# HATv1.net
KiCad netlist of a schematic drawn in EAGLE
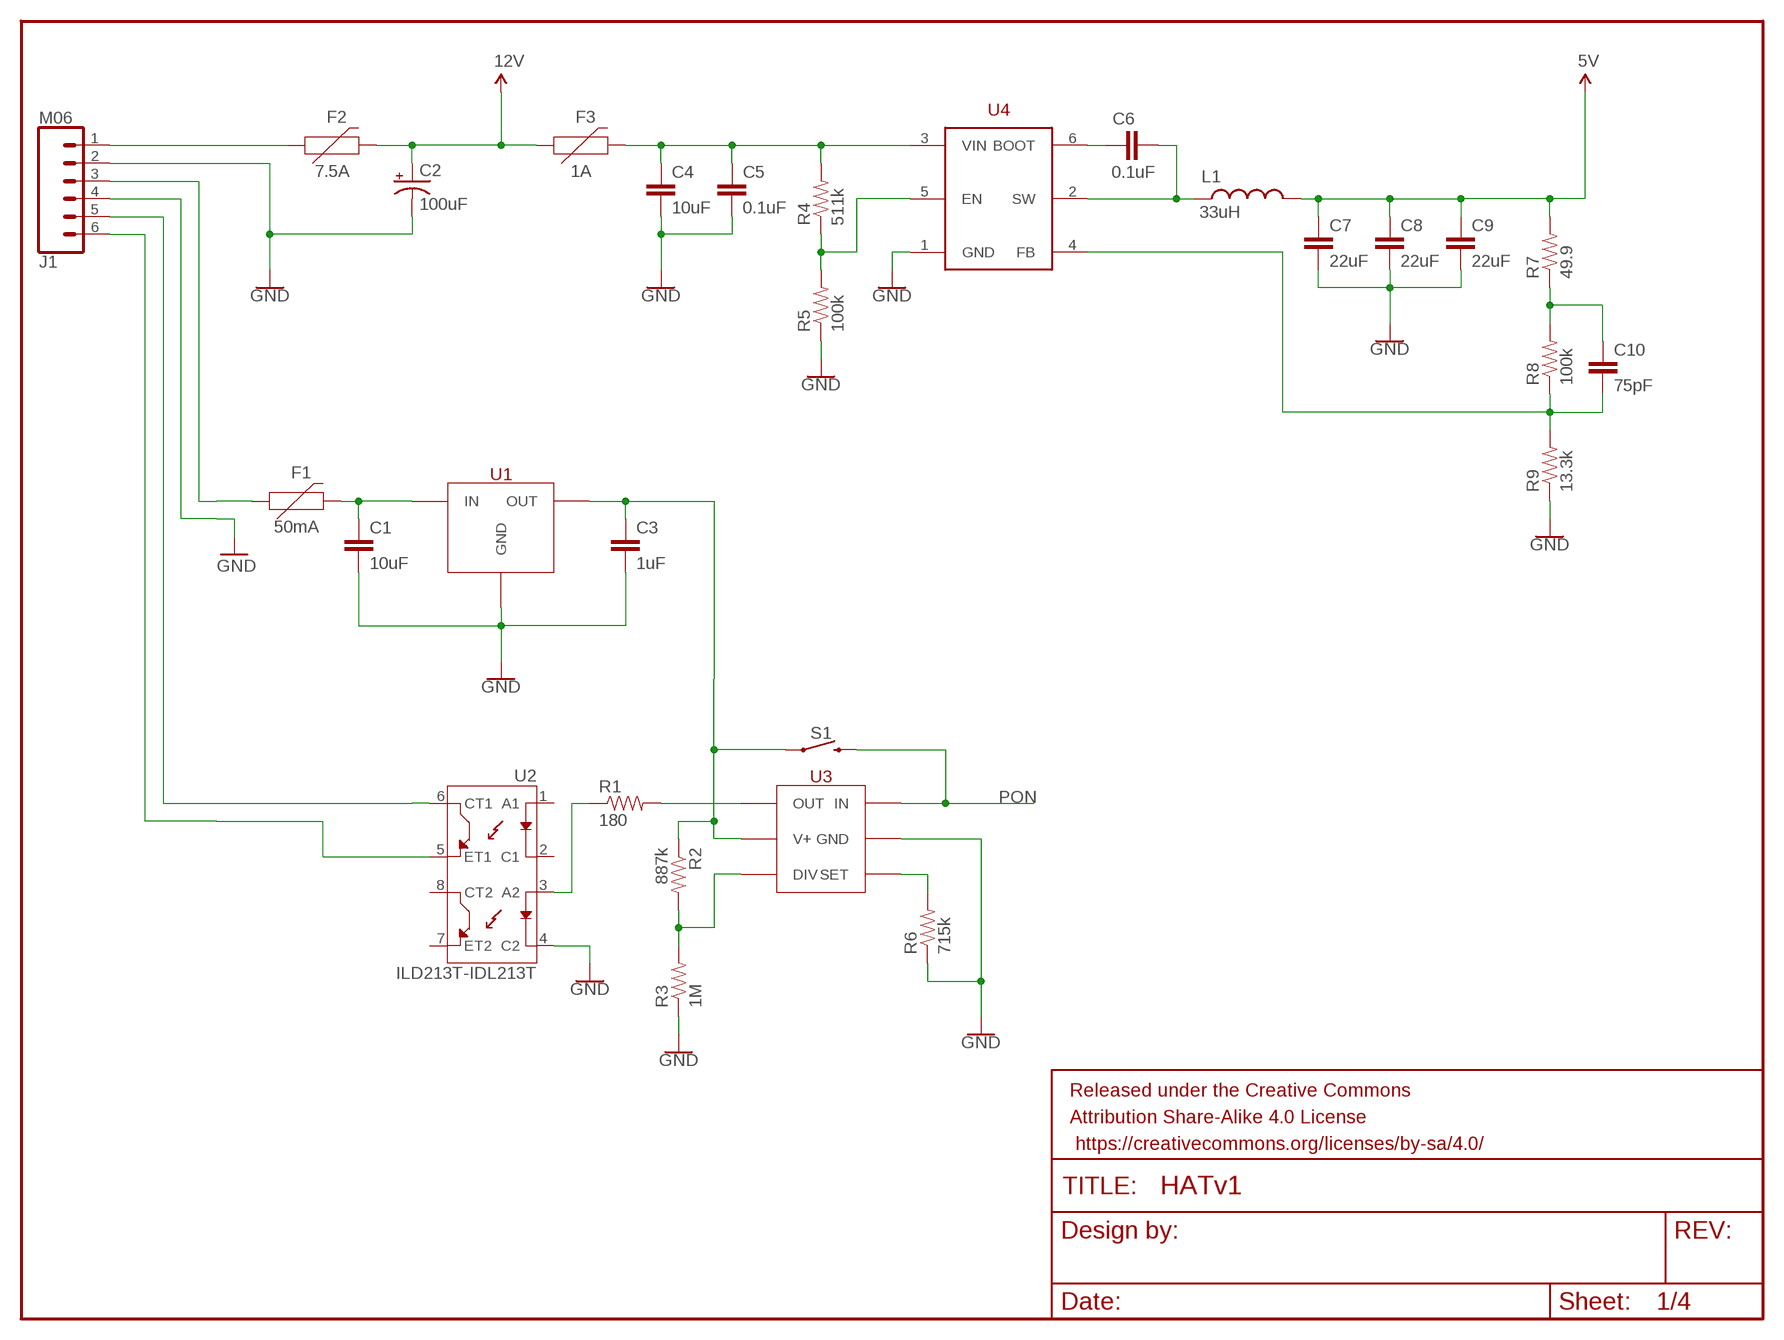
[diagram p0: schematic, sheet 1]
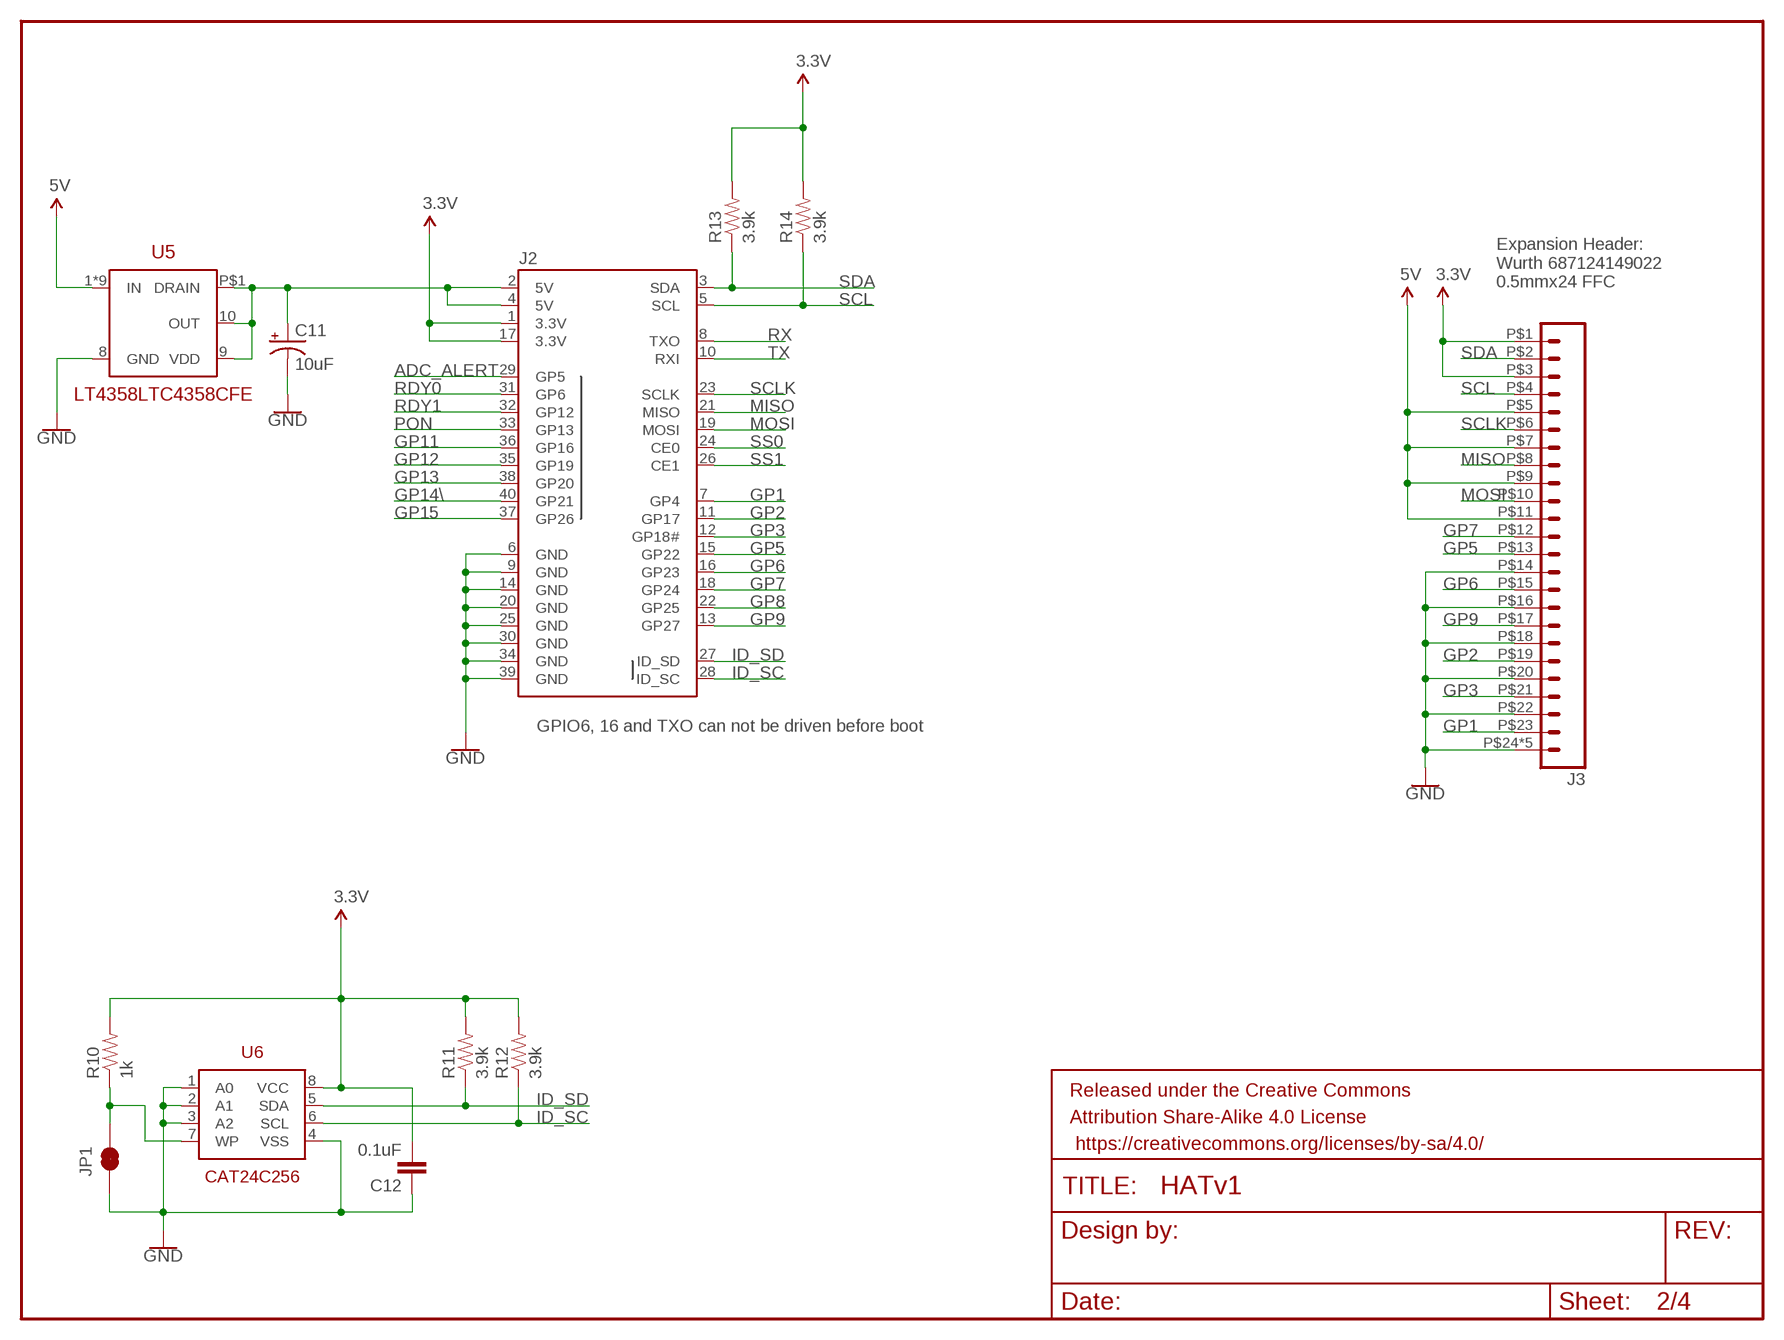
[diagram p1: schematic, sheet 2]
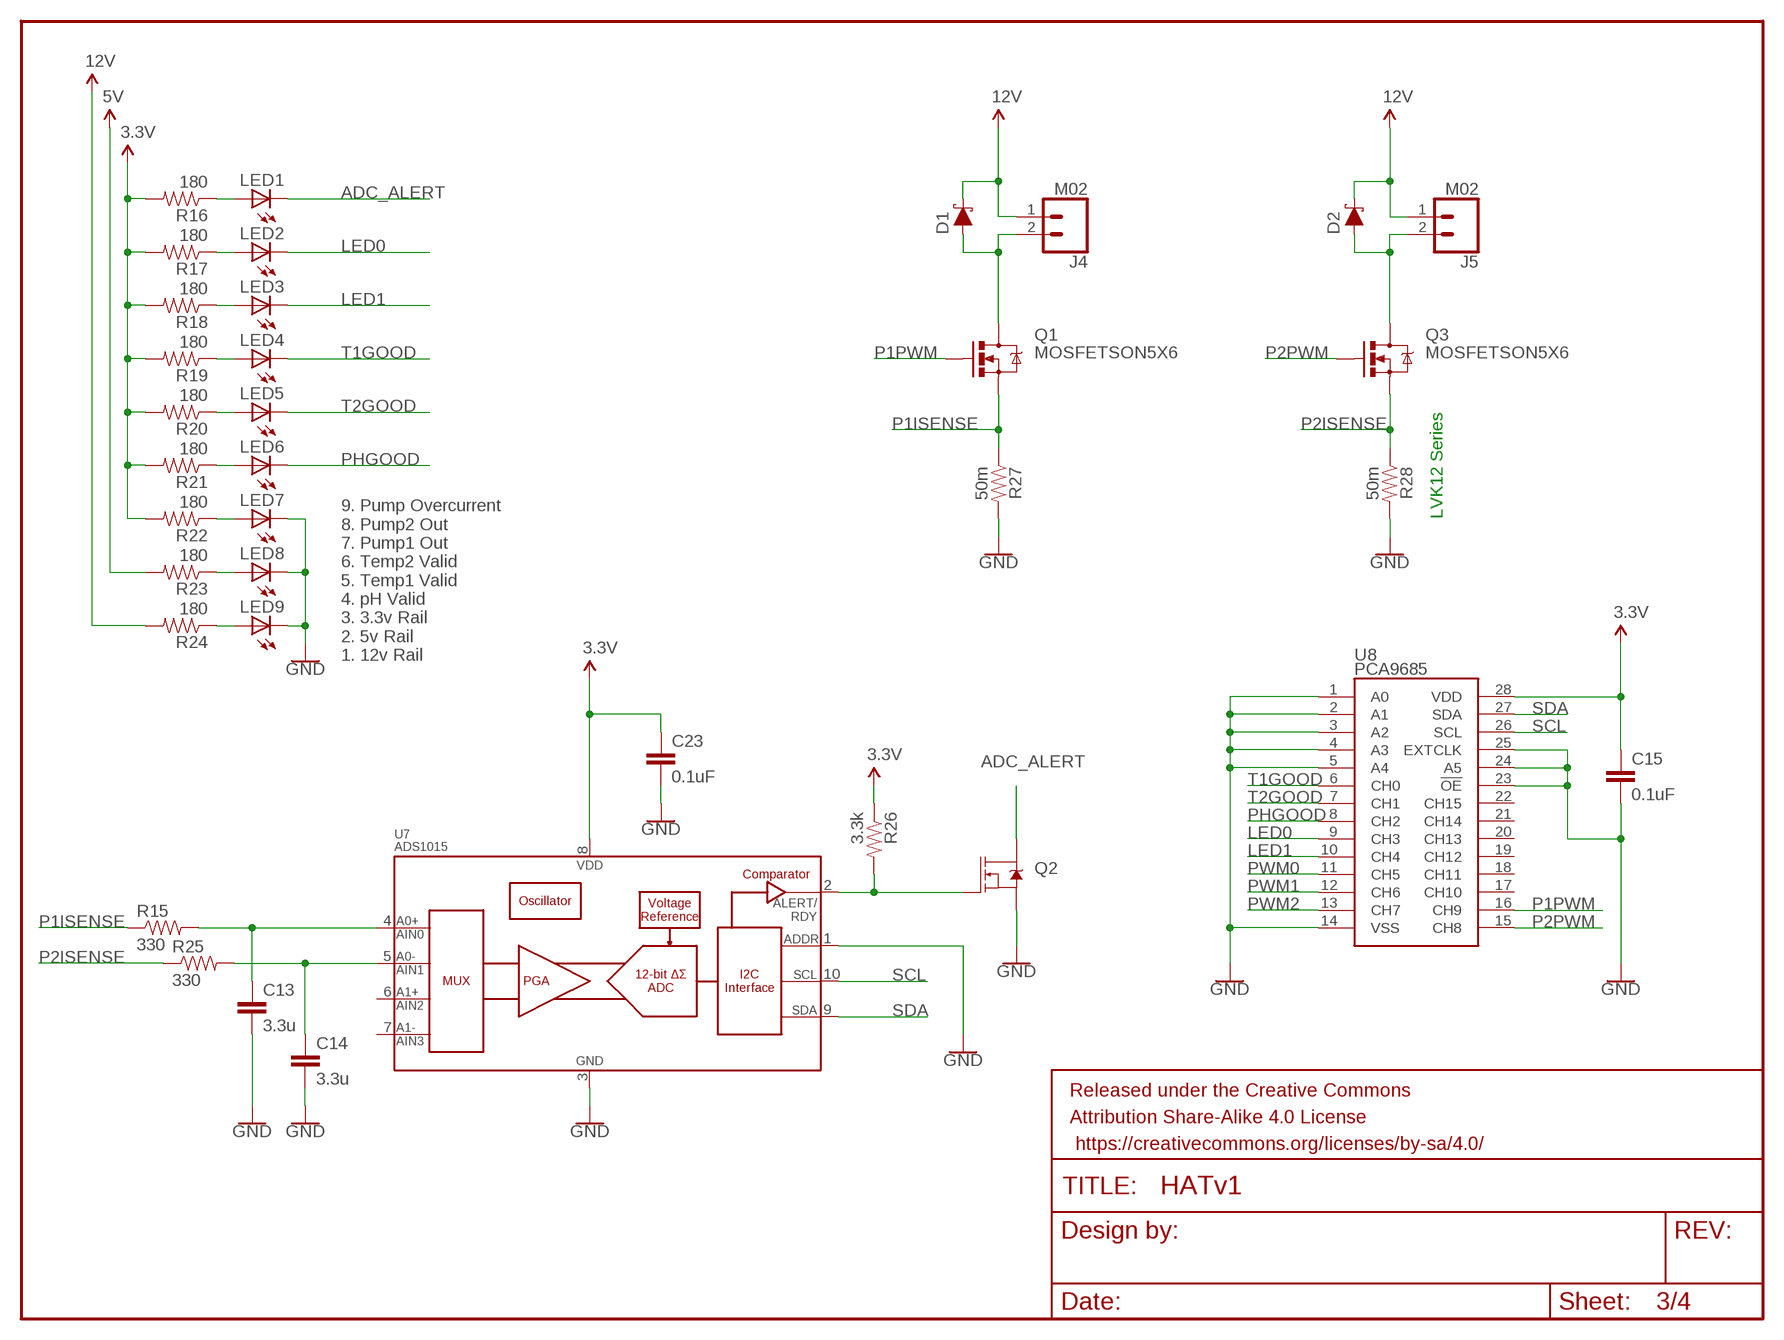
[diagram p2: schematic, sheet 3]
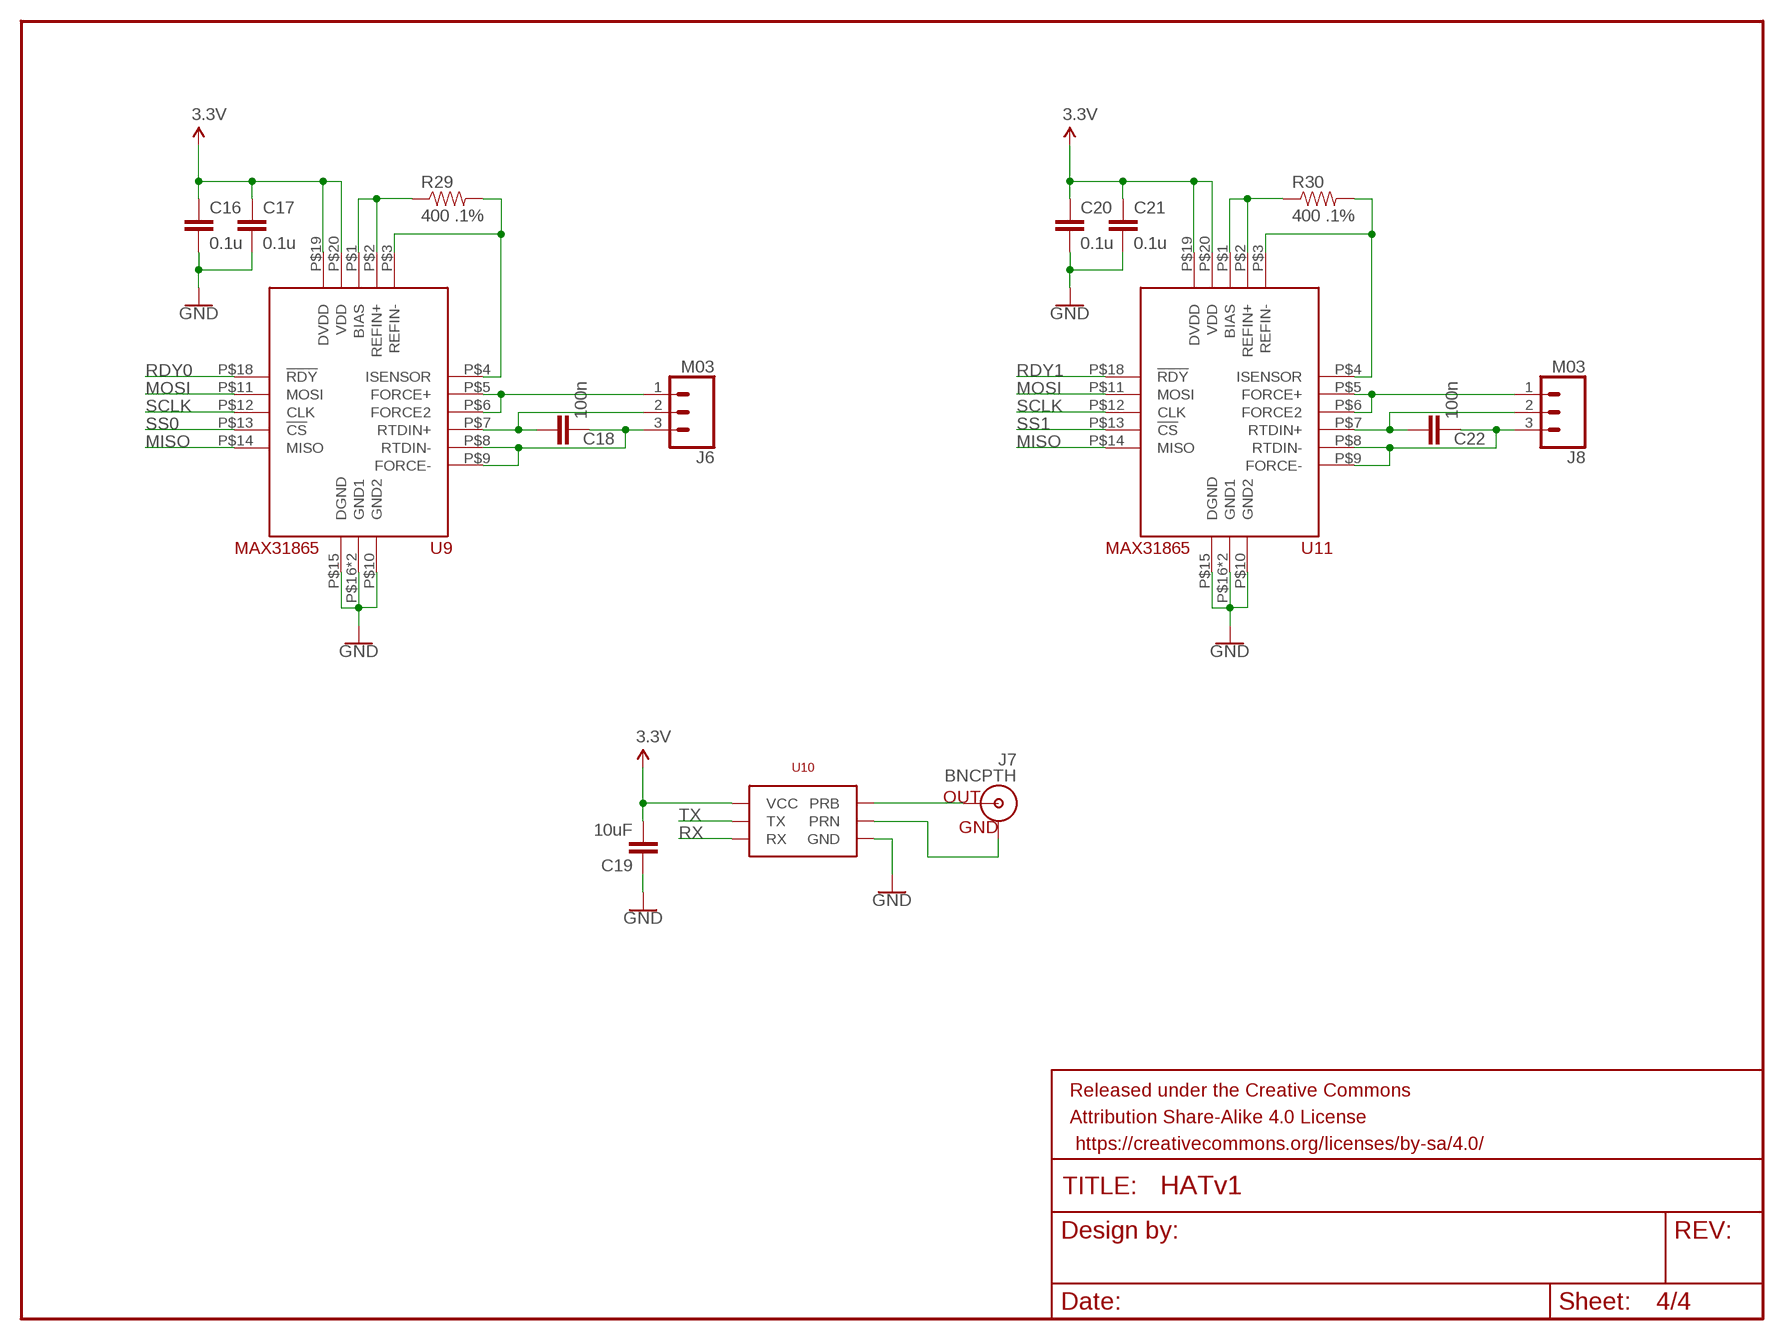
[diagram p3: schematic, sheet 4]

(export (version "E")
  (design (tool "Eeschema 10.0.6"))
  (components
    (comp (ref "C16")
      (value "0.1u")
      (footprint "eagle-import:0603-CAP")
      (libsource (lib "eagle-import") (part "CAP0603-CAP"))
    )
    (comp (ref "C17")
      (value "0.1u")
      (footprint "eagle-import:0603-CAP")
      (libsource (lib "eagle-import") (part "CAP0603-CAP"))
    )
    (comp (ref "C18")
      (value "100n")
      (footprint "eagle-import:0603-CAP")
      (libsource (lib "eagle-import") (part "CAP0603-CAP"))
    )
    (comp (ref "C19")
      (value "10uF")
      (footprint "eagle-import:1206")
      (libsource (lib "eagle-import") (part "10UF-1206-6.3V-20%"))
    )
    (comp (ref "C20")
      (value "0.1u")
      (footprint "eagle-import:0603-CAP")
      (libsource (lib "eagle-import") (part "CAP0603-CAP"))
    )
    (comp (ref "C21")
      (value "0.1u")
      (footprint "eagle-import:0603-CAP")
      (libsource (lib "eagle-import") (part "CAP0603-CAP"))
    )
    (comp (ref "C22")
      (value "100n")
      (footprint "eagle-import:0603-CAP")
      (libsource (lib "eagle-import") (part "CAP0603-CAP"))
    )
    (comp (ref "FRAME4")
      (value "FRAME-LETTERNO_PACKAGE")
      (footprint "eagle-import:DUMMY")
      (fields (field (name "DESIGNER") "Nobody"))
      (libsource (lib "eagle-import") (part "SparkFun-Aesthetics_507_FRAME-LETTERNO_PACKAGE"))
    )
    (comp (ref "J6")
      (value "M03")
      (footprint "eagle-import:1X03")
      (libsource (lib "eagle-import") (part "M03"))
    )
    (comp (ref "J7")
      (value "BNCPTH")
      (footprint "eagle-import:BNC")
      (libsource (lib "eagle-import") (part "BNCPTH"))
    )
    (comp (ref "J8")
      (value "M03")
      (footprint "eagle-import:1X03")
      (libsource (lib "eagle-import") (part "M03"))
    )
    (comp (ref "R29")
      (value "400 .1%")
      (footprint "eagle-import:0603-RES")
      (libsource (lib "eagle-import") (part "RESISTOR0603-RES"))
    )
    (comp (ref "R30")
      (value "400 .1%")
      (footprint "eagle-import:0603-RES")
      (libsource (lib "eagle-import") (part "RESISTOR0603-RES"))
    )
    (comp (ref "U9")
      (value "MAX31865")
      (footprint "eagle-import:TQFN20")
      (libsource (lib "eagle-import") (part "MAX31865"))
    )
    (comp (ref "U10")
      (value "EZOPH")
      (footprint "eagle-import:EZOPH")
      (libsource (lib "eagle-import") (part "EZOPH"))
    )
    (comp (ref "U11")
      (value "MAX31865")
      (footprint "eagle-import:TQFN20")
      (libsource (lib "eagle-import") (part "MAX31865"))
    )
    (comp (ref "C13")
      (value "3.3u")
      (footprint "eagle-import:0603")
      (libsource (lib "eagle-import") (part "2.2UF-0603-10V-20%"))
    )
    (comp (ref "C14")
      (value "3.3u")
      (footprint "eagle-import:0603")
      (libsource (lib "eagle-import") (part "2.2UF-0603-10V-20%"))
    )
    (comp (ref "C15")
      (value "0.1uF")
      (footprint "eagle-import:0603-CAP")
      (libsource (lib "eagle-import") (part "CAP0603-CAP"))
    )
    (comp (ref "C23")
      (value "0.1uF")
      (footprint "eagle-import:0603-CAP")
      (libsource (lib "eagle-import") (part "CAP0603-CAP"))
    )
    (comp (ref "D1")
      (value "DIODE-SCHOTTKY-B340A")
      (footprint "eagle-import:SMA-DIODE")
      (libsource (lib "eagle-import") (part "DIODE-SCHOTTKY-B340A"))
    )
    (comp (ref "D2")
      (value "DIODE-SCHOTTKY-B340A")
      (footprint "eagle-import:SMA-DIODE")
      (libsource (lib "eagle-import") (part "DIODE-SCHOTTKY-B340A"))
    )
    (comp (ref "FRAME3")
      (value "FRAME-LETTERNO_PACKAGE")
      (footprint "eagle-import:DUMMY")
      (fields (field (name "DESIGNER") "Nobody"))
      (libsource (lib "eagle-import") (part "FRAME-LETTERNO_PACKAGE"))
    )
    (comp (ref "J4")
      (value "M02")
      (footprint "eagle-import:SCREWTERMINAL-3.5MM-2")
      (libsource (lib "eagle-import") (part "M02"))
    )
    (comp (ref "J5")
      (value "M02")
      (footprint "eagle-import:SCREWTERMINAL-3.5MM-2")
      (libsource (lib "eagle-import") (part "M02"))
    )
    (comp (ref "LED1")
      (value "LEDCHIP-LED0603")
      (footprint "eagle-import:CHIP-LED0603")
      (libsource (lib "eagle-import") (part "LEDCHIP-LED0603"))
    )
    (comp (ref "LED2")
      (value "LEDCHIP-LED0603")
      (footprint "eagle-import:CHIP-LED0603")
      (libsource (lib "eagle-import") (part "LEDCHIP-LED0603"))
    )
    (comp (ref "LED3")
      (value "LEDCHIP-LED0603")
      (footprint "eagle-import:CHIP-LED0603")
      (libsource (lib "eagle-import") (part "LEDCHIP-LED0603"))
    )
    (comp (ref "LED4")
      (value "LEDCHIP-LED0603")
      (footprint "eagle-import:CHIP-LED0603")
      (libsource (lib "eagle-import") (part "LEDCHIP-LED0603"))
    )
    (comp (ref "LED5")
      (value "LEDCHIP-LED0603")
      (footprint "eagle-import:CHIP-LED0603")
      (libsource (lib "eagle-import") (part "LEDCHIP-LED0603"))
    )
    (comp (ref "LED6")
      (value "LEDCHIP-LED0603")
      (footprint "eagle-import:CHIP-LED0603")
      (libsource (lib "eagle-import") (part "LEDCHIP-LED0603"))
    )
    (comp (ref "LED7")
      (value "LEDCHIP-LED0603")
      (footprint "eagle-import:CHIP-LED0603")
      (libsource (lib "eagle-import") (part "LEDCHIP-LED0603"))
    )
    (comp (ref "LED8")
      (value "LEDCHIP-LED0603")
      (footprint "eagle-import:CHIP-LED0603")
      (libsource (lib "eagle-import") (part "LEDCHIP-LED0603"))
    )
    (comp (ref "LED9")
      (value "LEDCHIP-LED0603")
      (footprint "eagle-import:CHIP-LED0603")
      (libsource (lib "eagle-import") (part "LEDCHIP-LED0603"))
    )
    (comp (ref "Q1")
      (value "MOSFETSON5X6")
      (footprint "eagle-import:SON5X6MM")
      (libsource (lib "eagle-import") (part "MOSFETSON5X6"))
    )
    (comp (ref "Q2")
      (value "MOSFET-NCH-BSS138")
      (footprint "eagle-import:SOT23-3")
      (libsource (lib "eagle-import") (part "MOSFET-NCH-BSS138"))
    )
    (comp (ref "Q3")
      (value "MOSFETSON5X6")
      (footprint "eagle-import:SON5X6MM")
      (libsource (lib "eagle-import") (part "MOSFETSON5X6"))
    )
    (comp (ref "R15")
      (value "330")
      (footprint "eagle-import:0603-RES")
      (libsource (lib "eagle-import") (part "RESISTOR0603-RES"))
    )
    (comp (ref "R16")
      (value "180")
      (footprint "eagle-import:0603-RES")
      (libsource (lib "eagle-import") (part "RESISTOR0603-RES"))
    )
    (comp (ref "R17")
      (value "180")
      (footprint "eagle-import:0603-RES")
      (libsource (lib "eagle-import") (part "RESISTOR0603-RES"))
    )
    (comp (ref "R18")
      (value "180")
      (footprint "eagle-import:0603-RES")
      (libsource (lib "eagle-import") (part "RESISTOR0603-RES"))
    )
    (comp (ref "R19")
      (value "180")
      (footprint "eagle-import:0603-RES")
      (libsource (lib "eagle-import") (part "RESISTOR0603-RES"))
    )
    (comp (ref "R20")
      (value "180")
      (footprint "eagle-import:0603-RES")
      (libsource (lib "eagle-import") (part "RESISTOR0603-RES"))
    )
    (comp (ref "R21")
      (value "180")
      (footprint "eagle-import:0603-RES")
      (libsource (lib "eagle-import") (part "RESISTOR0603-RES"))
    )
    (comp (ref "R22")
      (value "180")
      (footprint "eagle-import:0603-RES")
      (libsource (lib "eagle-import") (part "RESISTOR0603-RES"))
    )
    (comp (ref "R23")
      (value "180")
      (footprint "eagle-import:0603-RES")
      (libsource (lib "eagle-import") (part "RESISTOR0603-RES"))
    )
    (comp (ref "R24")
      (value "180")
      (footprint "eagle-import:0603-RES")
      (libsource (lib "eagle-import") (part "RESISTOR0603-RES"))
    )
    (comp (ref "R25")
      (value "330")
      (footprint "eagle-import:0603-RES")
      (libsource (lib "eagle-import") (part "RESISTOR0603-RES"))
    )
    (comp (ref "R26")
      (value "3.3k")
      (footprint "eagle-import:0603-RES")
      (libsource (lib "eagle-import") (part "RESISTOR0603-RES"))
    )
    (comp (ref "R27")
      (value "50m")
      (footprint "eagle-import:1206")
      (libsource (lib "eagle-import") (part "SparkFun-Resistors_532_RESISTOR1206"))
    )
    (comp (ref "R28")
      (value "50m")
      (footprint "eagle-import:1206")
      (libsource (lib "eagle-import") (part "SparkFun-Resistors_532_RESISTOR1206"))
    )
    (comp (ref "U7")
      (value "ADS1015")
      (footprint "eagle-import:MSOP10")
      (libsource (lib "eagle-import") (part "ADS1015"))
    )
    (comp (ref "U8")
      (value "PCA9685")
      (footprint "eagle-import:TSSOP-28_4MM")
      (libsource (lib "eagle-import") (part "PCA9685"))
    )
    (comp (ref "C11")
      (value "10uF")
      (footprint "eagle-import:EIA3216")
      (libsource (lib "eagle-import") (part "10UF-POLAR-EIA3216-16V-10%(TANT)"))
    )
    (comp (ref "C12")
      (value "0.1uF")
      (footprint "eagle-import:0603-CAP")
      (libsource (lib "eagle-import") (part "CAP0603-CAP"))
    )
    (comp (ref "FRAME2")
      (value "FRAME-LETTERNO_PACKAGE")
      (footprint "eagle-import:DUMMY")
      (fields (field (name "DESIGNER") "Nobody"))
      (libsource (lib "eagle-import") (part "SparkFun-Aesthetics_507_FRAME-LETTERNO_PACKAGE"))
    )
    (comp (ref "J2")
      (value "RASPBERRYPI-40-PIN-GPIO2X20PASSTHROUGH")
      (footprint "eagle-import:1X24SAMTEC")
      (libsource (lib "eagle-import") (part "RASPBERRYPI-40-PIN-GPIO2X20PASSTHROUGH"))
    )
    (comp (ref "J3")
      (value "M24FFC")
      (footprint "eagle-import:FFC_24")
      (libsource (lib "eagle-import") (part "M24FFC"))
    )
    (comp (ref "JP1")
      (value "JUMPER-PAD-2-NC_BY_TRACE")
      (footprint "eagle-import:PAD-JUMPER-2-NC_BY_TRACE_YES_SILK")
      (libsource (lib "eagle-import") (part "JUMPER-PAD-2-NC_BY_TRACE"))
    )
    (comp (ref "R10")
      (value "1k")
      (footprint "eagle-import:0603-RES")
      (libsource (lib "eagle-import") (part "RESISTOR0603-RES"))
    )
    (comp (ref "R11")
      (value "3.9k")
      (footprint "eagle-import:0603-RES")
      (libsource (lib "eagle-import") (part "RESISTOR0603-RES"))
    )
    (comp (ref "R12")
      (value "3.9k")
      (footprint "eagle-import:0603-RES")
      (libsource (lib "eagle-import") (part "RESISTOR0603-RES"))
    )
    (comp (ref "R13")
      (value "3.9k")
      (footprint "eagle-import:0603-RES")
      (libsource (lib "eagle-import") (part "RESISTOR0603-RES"))
    )
    (comp (ref "R14")
      (value "3.9k")
      (footprint "eagle-import:0603-RES")
      (libsource (lib "eagle-import") (part "RESISTOR0603-RES"))
    )
    (comp (ref "U5")
      (value "LT4358LTC4358CFE")
      (footprint "eagle-import:TSSOP-16")
      (libsource (lib "eagle-import") (part "LT4358LTC4358CFE"))
    )
    (comp (ref "U6")
      (value "CAT24C256")
      (footprint "eagle-import:SO8")
      (libsource (lib "eagle-import") (part "CAT24C256"))
    )
    (comp (ref "C1")
      (value "10uF")
      (footprint "eagle-import:0805")
      (libsource (lib "eagle-import") (part "CAP0805"))
    )
    (comp (ref "C2")
      (value "100uF")
      (footprint "eagle-import:PANASONIC_E")
      (libsource (lib "eagle-import") (part "CAP_POLE"))
    )
    (comp (ref "C3")
      (value "1uF")
      (footprint "eagle-import:0603-CAP")
      (libsource (lib "eagle-import") (part "CAP0603-CAP"))
    )
    (comp (ref "C4")
      (value "10uF")
      (footprint "eagle-import:0805")
      (libsource (lib "eagle-import") (part "CAP0805"))
    )
    (comp (ref "C5")
      (value "0.1uF")
      (footprint "eagle-import:0603-CAP")
      (libsource (lib "eagle-import") (part "CAP0603-CAP"))
    )
    (comp (ref "C6")
      (value "0.1uF")
      (footprint "eagle-import:0603-CAP")
      (libsource (lib "eagle-import") (part "CAP0603-CAP"))
    )
    (comp (ref "C7")
      (value "22uF")
      (footprint "eagle-import:1210")
      (libsource (lib "eagle-import") (part "CAP1210"))
    )
    (comp (ref "C8")
      (value "22uF")
      (footprint "eagle-import:1210")
      (libsource (lib "eagle-import") (part "CAP1210"))
    )
    (comp (ref "C9")
      (value "22uF")
      (footprint "eagle-import:1210")
      (libsource (lib "eagle-import") (part "CAP1210"))
    )
    (comp (ref "C10")
      (value "75pF")
      (footprint "eagle-import:0603-CAP")
      (libsource (lib "eagle-import") (part "CAP0603-CAP"))
    )
    (comp (ref "F1")
      (value "50mA")
      (footprint "eagle-import:PTH")
      (libsource (lib "eagle-import") (part "PPTC_PTH"))
    )
    (comp (ref "F2")
      (value "7.5A")
      (footprint "eagle-import:1206")
      (libsource (lib "eagle-import") (part "PPTC_HALF-AMP"))
    )
    (comp (ref "F3")
      (value "1A")
      (footprint "eagle-import:2010")
      (libsource (lib "eagle-import") (part "PTC"))
    )
    (comp (ref "FRAME1")
      (value "FRAME-LETTERNO_PACKAGE")
      (footprint "eagle-import:DUMMY")
      (fields (field (name "DESIGNER") "Nobody"))
      (libsource (lib "eagle-import") (part "FRAME-LETTERNO_PACKAGE"))
    )
    (comp (ref "J1")
      (value "M06")
      (footprint "eagle-import:SCREWTERMINAL-3.5MM-6")
      (libsource (lib "eagle-import") (part "M06"))
    )
    (comp (ref "L1")
      (value "33uH")
      (footprint "eagle-import:SRP1265A")
      (libsource (lib "eagle-import") (part "INDUCTORSRP1265"))
    )
    (comp (ref "R1")
      (value "180")
      (footprint "eagle-import:0603-RES")
      (libsource (lib "eagle-import") (part "RESISTOR0603-RES"))
    )
    (comp (ref "R2")
      (value "887k")
      (footprint "eagle-import:0603-RES")
      (libsource (lib "eagle-import") (part "RESISTOR0603-RES"))
    )
    (comp (ref "R3")
      (value "1M")
      (footprint "eagle-import:0603-RES")
      (libsource (lib "eagle-import") (part "RESISTOR0603-RES"))
    )
    (comp (ref "R4")
      (value "511k")
      (footprint "eagle-import:0603-RES")
      (libsource (lib "eagle-import") (part "RESISTOR0603-RES"))
    )
    (comp (ref "R5")
      (value "100k")
      (footprint "eagle-import:0603-RES")
      (libsource (lib "eagle-import") (part "RESISTOR0603-RES"))
    )
    (comp (ref "R6")
      (value "715k")
      (footprint "eagle-import:0603-RES")
      (libsource (lib "eagle-import") (part "RESISTOR0603-RES"))
    )
    (comp (ref "R7")
      (value "49.9")
      (footprint "eagle-import:0603-RES")
      (libsource (lib "eagle-import") (part "RESISTOR0603-RES"))
    )
    (comp (ref "R8")
      (value "100k")
      (footprint "eagle-import:0603-RES")
      (libsource (lib "eagle-import") (part "RESISTOR0603-RES"))
    )
    (comp (ref "R9")
      (value "13.3k")
      (footprint "eagle-import:0603-RES")
      (libsource (lib "eagle-import") (part "RESISTOR0603-RES"))
    )
    (comp (ref "S1")
      (value "MOMENTARY-SWITCH-SPST-SMD-12MM")
      (footprint "eagle-import:TACTILE_SWITCH_SMD_12MM")
      (libsource (lib "eagle-import") (part "MOMENTARY-SWITCH-SPST-SMD-12MM"))
    )
    (comp (ref "U1")
      (value "NCP715")
      (footprint "eagle-import:SC70")
      (libsource (lib "eagle-import") (part "NCP715"))
    )
    (comp (ref "U2")
      (value "ILD213T-IDL213T")
      (footprint "eagle-import:SO08")
      (libsource (lib "eagle-import") (part "ILD213T-IDL213T"))
    )
    (comp (ref "U3")
      (value "LT6994")
      (footprint "eagle-import:SOT23-6")
      (libsource (lib "eagle-import") (part "LT6994"))
    )
    (comp (ref "U4")
      (value "TPS54302")
      (footprint "eagle-import:SOT23-6")
      (libsource (lib "eagle-import") (part "TPS54302"))
    )
  )
  (nets
    (net (code "1") (name "3.3V") (class "Default")
      (node (ref "C12") (pin "2") (pinfunction "2_2") (pintype "passive"))
      (node (ref "C15") (pin "1") (pinfunction "1_1") (pintype "passive"))
      (node (ref "C16") (pin "1") (pinfunction "1_1") (pintype "passive"))
      (node (ref "C17") (pin "1") (pinfunction "1_1") (pintype "passive"))
      (node (ref "C19") (pin "2") (pinfunction "2_2") (pintype "passive"))
      (node (ref "C20") (pin "1") (pinfunction "1_1") (pintype "passive"))
      (node (ref "C21") (pin "1") (pinfunction "1_1") (pintype "passive"))
      (node (ref "C23") (pin "1") (pinfunction "1_1") (pintype "passive"))
      (node (ref "J2") (pin "1") (pinfunction "3.3V_1") (pintype "power_in"))
      (node (ref "J2") (pin "17") (pinfunction "3.3V_17") (pintype "power_in"))
      (node (ref "J3") (pin "P$1") (pinfunction "2_P$1") (pintype "passive"))
      (node (ref "J3") (pin "P$3") (pinfunction "4_P$3") (pintype "passive"))
      (node (ref "R10") (pin "2") (pinfunction "2_2") (pintype "passive"))
      (node (ref "R11") (pin "2") (pinfunction "2_2") (pintype "passive"))
      (node (ref "R12") (pin "2") (pinfunction "2_2") (pintype "passive"))
      (node (ref "R13") (pin "2") (pinfunction "2_2") (pintype "passive"))
      (node (ref "R14") (pin "2") (pinfunction "2_2") (pintype "passive"))
      (node (ref "R16") (pin "2") (pinfunction "2_2") (pintype "passive"))
      (node (ref "R17") (pin "2") (pinfunction "2_2") (pintype "passive"))
      (node (ref "R18") (pin "2") (pinfunction "2_2") (pintype "passive"))
      (node (ref "R19") (pin "2") (pinfunction "2_2") (pintype "passive"))
      (node (ref "R20") (pin "2") (pinfunction "2_2") (pintype "passive"))
      (node (ref "R21") (pin "2") (pinfunction "2_2") (pintype "passive"))
      (node (ref "R22") (pin "2") (pinfunction "2_2") (pintype "passive"))
      (node (ref "R26") (pin "1") (pinfunction "1_1") (pintype "passive"))
      (node (ref "U10") (pin "VCC") (pinfunction "VCC_VCC") (pintype "bidirectional"))
      (node (ref "U11") (pin "P$19") (pinfunction "DVDD_P$19") (pintype "bidirectional"))
      (node (ref "U11") (pin "P$20") (pinfunction "VDD_P$20") (pintype "bidirectional"))
      (node (ref "U6") (pin "8") (pinfunction "VCC_8") (pintype "power_in"))
      (node (ref "U7") (pin "8") (pinfunction "VDD_8") (pintype "bidirectional"))
      (node (ref "U8") (pin "28") (pinfunction "VDD_28") (pintype "bidirectional"))
      (node (ref "U9") (pin "P$19") (pinfunction "DVDD_P$19") (pintype "bidirectional"))
      (node (ref "U9") (pin "P$20") (pinfunction "VDD_P$20") (pintype "bidirectional"))
    )
    (net (code "2") (name "5V") (class "Default")
      (node (ref "C7") (pin "1") (pinfunction "1_1") (pintype "passive"))
      (node (ref "C8") (pin "1") (pinfunction "1_1") (pintype "passive"))
      (node (ref "C9") (pin "1") (pinfunction "1_1") (pintype "passive"))
      (node (ref "J3") (pin "P$11") (pinfunction "12_P$11") (pintype "passive"))
      (node (ref "J3") (pin "P$5") (pinfunction "6_P$5") (pintype "passive"))
      (node (ref "J3") (pin "P$7") (pinfunction "8_P$7") (pintype "passive"))
      (node (ref "J3") (pin "P$9") (pinfunction "10_P$9") (pintype "passive"))
      (node (ref "L1") (pin "P$2") (pinfunction "2_P$2") (pintype "passive"))
      (node (ref "R23") (pin "2") (pinfunction "2_2") (pintype "passive"))
      (node (ref "R7") (pin "2") (pinfunction "2_2") (pintype "passive"))
      (node (ref "U5") (pin "1") (pinfunction "IN_1") (pintype "bidirectional"))
      (node (ref "U5") (pin "12") (pinfunction "IN_12") (pintype "bidirectional"))
      (node (ref "U5") (pin "13") (pinfunction "IN_13") (pintype "bidirectional"))
      (node (ref "U5") (pin "14") (pinfunction "IN_14") (pintype "bidirectional"))
      (node (ref "U5") (pin "15") (pinfunction "IN_15") (pintype "bidirectional"))
      (node (ref "U5") (pin "16") (pinfunction "IN_16") (pintype "bidirectional"))
      (node (ref "U5") (pin "2") (pinfunction "IN_2") (pintype "bidirectional"))
      (node (ref "U5") (pin "3") (pinfunction "IN_3") (pintype "bidirectional"))
      (node (ref "U5") (pin "4") (pinfunction "IN_4") (pintype "bidirectional"))
    )
    (net (code "3") (name "12V") (class "Default")
      (node (ref "C2") (pin "+") (pinfunction "+_+") (pintype "passive"))
      (node (ref "D1") (pin "C") (pinfunction "C_C") (pintype "passive"))
      (node (ref "D2") (pin "C") (pinfunction "C_C") (pintype "passive"))
      (node (ref "F2") (pin "2") (pinfunction "2_2") (pintype "bidirectional"))
      (node (ref "F3") (pin "1") (pinfunction "1_1") (pintype "bidirectional"))
      (node (ref "J4") (pin "1") (pinfunction "1_1") (pintype "passive"))
      (node (ref "J5") (pin "1") (pinfunction "1_1") (pintype "passive"))
      (node (ref "R24") (pin "2") (pinfunction "2_2") (pintype "passive"))
    )
    (net (code "4") (name "ADC_ALERT") (class "Default")
      (node (ref "J2") (pin "29") (pinfunction "GP5_29") (pintype "bidirectional"))
      (node (ref "LED1") (pin "C") (pinfunction "C_C") (pintype "passive"))
      (node (ref "Q2") (pin "3") (pinfunction "D_3") (pintype "bidirectional"))
    )
    (net (code "5") (name "GND") (class "Default")
      (node (ref "C1") (pin "2") (pinfunction "2_2") (pintype "passive"))
      (node (ref "C11") (pin "-") (pinfunction "-_-") (pintype "passive"))
      (node (ref "C12") (pin "1") (pinfunction "1_1") (pintype "passive"))
      (node (ref "C13") (pin "2") (pinfunction "2_2") (pintype "passive"))
      (node (ref "C14") (pin "2") (pinfunction "2_2") (pintype "passive"))
      (node (ref "C15") (pin "2") (pinfunction "2_2") (pintype "passive"))
      (node (ref "C16") (pin "2") (pinfunction "2_2") (pintype "passive"))
      (node (ref "C17") (pin "2") (pinfunction "2_2") (pintype "passive"))
      (node (ref "C19") (pin "1") (pinfunction "1_1") (pintype "passive"))
      (node (ref "C2") (pin "-") (pinfunction "-_-") (pintype "passive"))
      (node (ref "C20") (pin "2") (pinfunction "2_2") (pintype "passive"))
      (node (ref "C21") (pin "2") (pinfunction "2_2") (pintype "passive"))
      (node (ref "C23") (pin "2") (pinfunction "2_2") (pintype "passive"))
      (node (ref "C3") (pin "2") (pinfunction "2_2") (pintype "passive"))
      (node (ref "C4") (pin "2") (pinfunction "2_2") (pintype "passive"))
      (node (ref "C5") (pin "2") (pinfunction "2_2") (pintype "passive"))
      (node (ref "C7") (pin "2") (pinfunction "2_2") (pintype "passive"))
      (node (ref "C8") (pin "2") (pinfunction "2_2") (pintype "passive"))
      (node (ref "C9") (pin "2") (pinfunction "2_2") (pintype "passive"))
      (node (ref "J1") (pin "2") (pinfunction "2_2") (pintype "passive"))
      (node (ref "J1") (pin "4") (pinfunction "4_4") (pintype "passive"))
      (node (ref "J2") (pin "14") (pinfunction "GND_14") (pintype "power_in"))
      (node (ref "J2") (pin "20") (pinfunction "GND_20") (pintype "power_in"))
      (node (ref "J2") (pin "25") (pinfunction "GND_25") (pintype "power_in"))
      (node (ref "J2") (pin "30") (pinfunction "GND_30") (pintype "power_in"))
      (node (ref "J2") (pin "34") (pinfunction "GND_34") (pintype "power_in"))
      (node (ref "J2") (pin "39") (pinfunction "GND_39") (pintype "power_in"))
      (node (ref "J2") (pin "6") (pinfunction "GND_6") (pintype "power_in"))
      (node (ref "J2") (pin "9") (pinfunction "GND_9") (pintype "power_in"))
      (node (ref "J3") (pin "P$14") (pinfunction "15_P$14") (pintype "passive"))
      (node (ref "J3") (pin "P$16") (pinfunction "17_P$16") (pintype "passive"))
      (node (ref "J3") (pin "P$18") (pinfunction "19_P$18") (pintype "passive"))
      (node (ref "J3") (pin "P$20") (pinfunction "21_P$20") (pintype "passive"))
      (node (ref "J3") (pin "P$22") (pinfunction "23_P$22") (pintype "passive"))
      (node (ref "J3") (pin "P$24") (pinfunction "25_P$24") (pintype "passive"))
      (node (ref "J3") (pin "P$25") (pinfunction "25_P$25") (pintype "passive"))
      (node (ref "J3") (pin "P$26") (pinfunction "25_P$26") (pintype "passive"))
      (node (ref "J3") (pin "P$27") (pinfunction "25_P$27") (pintype "passive"))
      (node (ref "J3") (pin "P$28") (pinfunction "25_P$28") (pintype "passive"))
      (node (ref "JP1") (pin "1") (pinfunction "1_1") (pintype "passive"))
      (node (ref "LED7") (pin "C") (pinfunction "C_C") (pintype "passive"))
      (node (ref "LED8") (pin "C") (pinfunction "C_C") (pintype "passive"))
      (node (ref "LED9") (pin "C") (pinfunction "C_C") (pintype "passive"))
      (node (ref "Q2") (pin "2") (pinfunction "S_2") (pintype "bidirectional"))
      (node (ref "R27") (pin "2") (pinfunction "2_2") (pintype "passive"))
      (node (ref "R28") (pin "2") (pinfunction "2_2") (pintype "passive"))
      (node (ref "R3") (pin "1") (pinfunction "1_1") (pintype "passive"))
      (node (ref "R5") (pin "1") (pinfunction "1_1") (pintype "passive"))
      (node (ref "R6") (pin "1") (pinfunction "1_1") (pintype "passive"))
      (node (ref "R9") (pin "1") (pinfunction "1_1") (pintype "passive"))
      (node (ref "U1") (pin "2") (pinfunction "GND_2") (pintype "bidirectional"))
      (node (ref "U10") (pin "GND") (pinfunction "GND_GND") (pintype "bidirectional"))
      (node (ref "U11") (pin "P$10") (pinfunction "GND2_P$10") (pintype "bidirectional"))
      (node (ref "U11") (pin "P$15") (pinfunction "DGND_P$15") (pintype "bidirectional"))
      (node (ref "U11") (pin "P$16") (pinfunction "GND1_P$16") (pintype "bidirectional"))
      (node (ref "U11") (pin "P$21") (pinfunction "GND1_P$21") (pintype "bidirectional"))
      (node (ref "U2") (pin "4") (pinfunction "C2_4") (pintype "bidirectional"))
      (node (ref "U3") (pin "2") (pinfunction "GND_2") (pintype "bidirectional"))
      (node (ref "U4") (pin "1") (pinfunction "GND_1") (pintype "bidirectional"))
      (node (ref "U5") (pin "8") (pinfunction "GND_8") (pintype "bidirectional"))
      (node (ref "U6") (pin "1") (pinfunction "A0_1") (pintype "bidirectional"))
      (node (ref "U6") (pin "2") (pinfunction "A1_2") (pintype "bidirectional"))
      (node (ref "U6") (pin "3") (pinfunction "A2_3") (pintype "bidirectional"))
      (node (ref "U6") (pin "4") (pinfunction "VSS_4") (pintype "power_in"))
      (node (ref "U7") (pin "1") (pinfunction "ADDR_1") (pintype "bidirectional"))
      (node (ref "U7") (pin "3") (pinfunction "VSS_3") (pintype "bidirectional"))
      (node (ref "U8") (pin "1") (pinfunction "A0_1") (pintype "bidirectional"))
      (node (ref "U8") (pin "14") (pinfunction "VSS_14") (pintype "bidirectional"))
      (node (ref "U8") (pin "2") (pinfunction "A1_2") (pintype "bidirectional"))
      (node (ref "U8") (pin "23") (pinfunction "~{OE}_23") (pintype "bidirectional"))
      (node (ref "U8") (pin "24") (pinfunction "A5_24") (pintype "bidirectional"))
      (node (ref "U8") (pin "25") (pinfunction "EXTCLK_25") (pintype "bidirectional"))
      (node (ref "U8") (pin "3") (pinfunction "A2_3") (pintype "bidirectional"))
      (node (ref "U8") (pin "4") (pinfunction "A3_4") (pintype "bidirectional"))
      (node (ref "U8") (pin "5") (pinfunction "A4_5") (pintype "bidirectional"))
      (node (ref "U9") (pin "P$10") (pinfunction "GND2_P$10") (pintype "bidirectional"))
      (node (ref "U9") (pin "P$15") (pinfunction "DGND_P$15") (pintype "bidirectional"))
      (node (ref "U9") (pin "P$16") (pinfunction "GND1_P$16") (pintype "bidirectional"))
      (node (ref "U9") (pin "P$21") (pinfunction "GND1_P$21") (pintype "bidirectional"))
    )
    (net (code "6") (name "GP1") (class "Default")
      (node (ref "J2") (pin "7") (pinfunction "GP4_7") (pintype "bidirectional"))
      (node (ref "J3") (pin "P$23") (pinfunction "24_P$23") (pintype "passive"))
    )
    (net (code "7") (name "GP2") (class "Default")
      (node (ref "J2") (pin "11") (pinfunction "GP17_11") (pintype "bidirectional"))
      (node (ref "J3") (pin "P$19") (pinfunction "20_P$19") (pintype "passive"))
    )
    (net (code "8") (name "GP3") (class "Default")
      (node (ref "J2") (pin "12") (pinfunction "GP18#_12") (pintype "bidirectional"))
      (node (ref "J3") (pin "P$21") (pinfunction "22_P$21") (pintype "passive"))
    )
    (net (code "9") (name "GP5") (class "Default")
      (node (ref "J2") (pin "15") (pinfunction "GP22_15") (pintype "bidirectional"))
      (node (ref "J3") (pin "P$13") (pinfunction "14_P$13") (pintype "passive"))
    )
    (net (code "10") (name "GP6") (class "Default")
      (node (ref "J2") (pin "16") (pinfunction "GP23_16") (pintype "bidirectional"))
      (node (ref "J3") (pin "P$15") (pinfunction "16_P$15") (pintype "passive"))
    )
    (net (code "11") (name "GP7") (class "Default")
      (node (ref "J2") (pin "18") (pinfunction "GP24_18") (pintype "bidirectional"))
      (node (ref "J3") (pin "P$12") (pinfunction "13_P$12") (pintype "passive"))
    )
    (net (code "12") (name "GP8") (class "Default")
      (node (ref "J2") (pin "22") (pinfunction "GP25_22") (pintype "bidirectional"))
    )
    (net (code "13") (name "GP9") (class "Default")
      (node (ref "J2") (pin "13") (pinfunction "GP27_13") (pintype "bidirectional"))
      (node (ref "J3") (pin "P$17") (pinfunction "18_P$17") (pintype "passive"))
    )
    (net (code "14") (name "GP11") (class "Default")
      (node (ref "J2") (pin "36") (pinfunction "GP16_36") (pintype "bidirectional"))
    )
    (net (code "15") (name "GP12") (class "Default")
      (node (ref "J2") (pin "35") (pinfunction "GP19_35") (pintype "bidirectional"))
    )
    (net (code "16") (name "GP13") (class "Default")
      (node (ref "J2") (pin "38") (pinfunction "GP20_38") (pintype "bidirectional"))
    )
    (net (code "17") (name "GP14\\") (class "Default")
      (node (ref "J2") (pin "40") (pinfunction "GP21_40") (pintype "bidirectional"))
    )
    (net (code "18") (name "GP15") (class "Default")
      (node (ref "J2") (pin "37") (pinfunction "GP26_37") (pintype "bidirectional"))
    )
    (net (code "19") (name "ID_SC") (class "Default")
      (node (ref "J2") (pin "28") (pinfunction "ID_SC_28") (pintype "bidirectional"))
      (node (ref "R12") (pin "1") (pinfunction "1_1") (pintype "passive"))
      (node (ref "U6") (pin "6") (pinfunction "SCL_6") (pintype "bidirectional"))
    )
    (net (code "20") (name "ID_SD") (class "Default")
      (node (ref "J2") (pin "27") (pinfunction "ID_SD_27") (pintype "bidirectional"))
      (node (ref "R11") (pin "1") (pinfunction "1_1") (pintype "passive"))
      (node (ref "U6") (pin "5") (pinfunction "SDA_5") (pintype "bidirectional"))
    )
    (net (code "21") (name "LED0") (class "Default")
      (node (ref "LED2") (pin "C") (pinfunction "C_C") (pintype "passive"))
      (node (ref "U8") (pin "9") (pinfunction "CH3_9") (pintype "bidirectional"))
    )
    (net (code "22") (name "LED1") (class "Default")
      (node (ref "LED3") (pin "C") (pinfunction "C_C") (pintype "passive"))
      (node (ref "U8") (pin "10") (pinfunction "CH4_10") (pintype "bidirectional"))
    )
    (net (code "23") (name "MISO") (class "Default")
      (node (ref "J2") (pin "21") (pinfunction "MISO_21") (pintype "input"))
      (node (ref "J3") (pin "P$8") (pinfunction "9_P$8") (pintype "passive"))
      (node (ref "U11") (pin "P$14") (pinfunction "MISO_P$14") (pintype "bidirectional"))
      (node (ref "U9") (pin "P$14") (pinfunction "MISO_P$14") (pintype "bidirectional"))
    )
    (net (code "24") (name "MOSI") (class "Default")
      (node (ref "J2") (pin "19") (pinfunction "MOSI_19") (pintype "output"))
      (node (ref "J3") (pin "P$10") (pinfunction "11_P$10") (pintype "passive"))
      (node (ref "U11") (pin "P$11") (pinfunction "MOSI_P$11") (pintype "bidirectional"))
      (node (ref "U9") (pin "P$11") (pinfunction "MOSI_P$11") (pintype "bidirectional"))
    )
    (net (code "25") (name "Net-(C10-Pad1)") (class "Default")
      (node (ref "C10") (pin "1") (pinfunction "1_1") (pintype "passive"))
      (node (ref "R7") (pin "1") (pinfunction "1_1") (pintype "passive"))
      (node (ref "R8") (pin "2") (pinfunction "2_2") (pintype "passive"))
    )
    (net (code "26") (name "Net-(D1-PadA)") (class "Default")
      (node (ref "D1") (pin "A") (pinfunction "A_A") (pintype "passive"))
      (node (ref "J4") (pin "2") (pinfunction "2_2") (pintype "passive"))
      (node (ref "Q1") (pin "P$5") (pinfunction "D_P$5") (pintype "passive"))
      (node (ref "Q1") (pin "P$6") (pinfunction "D_P$6") (pintype "passive"))
      (node (ref "Q1") (pin "P$7") (pinfunction "D_P$7") (pintype "passive"))
      (node (ref "Q1") (pin "P$8") (pinfunction "D_P$8") (pintype "passive"))
      (node (ref "Q1") (pin "P$9") (pinfunction "D_P$9") (pintype "passive"))
    )
    (net (code "27") (name "Net-(D2-PadA)") (class "Default")
      (node (ref "D2") (pin "A") (pinfunction "A_A") (pintype "passive"))
      (node (ref "J5") (pin "2") (pinfunction "2_2") (pintype "passive"))
      (node (ref "Q3") (pin "P$5") (pinfunction "D_P$5") (pintype "passive"))
      (node (ref "Q3") (pin "P$6") (pinfunction "D_P$6") (pintype "passive"))
      (node (ref "Q3") (pin "P$7") (pinfunction "D_P$7") (pintype "passive"))
      (node (ref "Q3") (pin "P$8") (pinfunction "D_P$8") (pintype "passive"))
      (node (ref "Q3") (pin "P$9") (pinfunction "D_P$9") (pintype "passive"))
    )
    (net (code "28") (name "Net-(F1-1)") (class "Default")
      (node (ref "F1") (pin "P$1") (pinfunction "1_P$1") (pintype "bidirectional"))
      (node (ref "J1") (pin "3") (pinfunction "3_3") (pintype "passive"))
    )
    (net (code "29") (name "Net-(F1-2)") (class "Default")
      (node (ref "C1") (pin "1") (pinfunction "1_1") (pintype "passive"))
      (node (ref "F1") (pin "P$2") (pinfunction "2_P$2") (pintype "bidirectional"))
      (node (ref "U1") (pin "4") (pinfunction "IN_4") (pintype "bidirectional"))
    )
    (net (code "30") (name "Net-(F2-Pad1)") (class "Default")
      (node (ref "F2") (pin "1") (pinfunction "1_1") (pintype "bidirectional"))
      (node (ref "J1") (pin "1") (pinfunction "1_1") (pintype "passive"))
    )
    (net (code "31") (name "Net-(J7-OUT)") (class "Default")
      (node (ref "J7") (pin "S") (pinfunction "OUT_S") (pintype "bidirectional"))
      (node (ref "U10") (pin "PRB") (pinfunction "PRB_PRB") (pintype "bidirectional"))
    )
    (net (code "32") (name "Net-(L1-1)") (class "Default")
      (node (ref "C6") (pin "2") (pinfunction "2_2") (pintype "passive"))
      (node (ref "L1") (pin "P$1") (pinfunction "1_P$1") (pintype "passive"))
      (node (ref "U4") (pin "2") (pinfunction "SW_2") (pintype "bidirectional"))
    )
    (net (code "33") (name "Net-(LED1-PadA)") (class "Default")
      (node (ref "LED1") (pin "A") (pinfunction "A_A") (pintype "passive"))
      (node (ref "R16") (pin "1") (pinfunction "1_1") (pintype "passive"))
    )
    (net (code "34") (name "Net-(LED2-PadA)") (class "Default")
      (node (ref "LED2") (pin "A") (pinfunction "A_A") (pintype "passive"))
      (node (ref "R17") (pin "1") (pinfunction "1_1") (pintype "passive"))
    )
    (net (code "35") (name "Net-(LED3-PadA)") (class "Default")
      (node (ref "LED3") (pin "A") (pinfunction "A_A") (pintype "passive"))
      (node (ref "R18") (pin "1") (pinfunction "1_1") (pintype "passive"))
    )
    (net (code "36") (name "Net-(LED4-PadA)") (class "Default")
      (node (ref "LED4") (pin "A") (pinfunction "A_A") (pintype "passive"))
      (node (ref "R19") (pin "1") (pinfunction "1_1") (pintype "passive"))
    )
    (net (code "37") (name "Net-(LED5-PadA)") (class "Default")
      (node (ref "LED5") (pin "A") (pinfunction "A_A") (pintype "passive"))
      (node (ref "R20") (pin "1") (pinfunction "1_1") (pintype "passive"))
    )
    (net (code "38") (name "Net-(LED6-PadA)") (class "Default")
      (node (ref "LED6") (pin "A") (pinfunction "A_A") (pintype "passive"))
      (node (ref "R21") (pin "1") (pinfunction "1_1") (pintype "passive"))
    )
    (net (code "39") (name "Net-(LED7-PadA)") (class "Default")
      (node (ref "LED7") (pin "A") (pinfunction "A_A") (pintype "passive"))
      (node (ref "R22") (pin "1") (pinfunction "1_1") (pintype "passive"))
    )
    (net (code "40") (name "Net-(LED8-PadA)") (class "Default")
      (node (ref "LED8") (pin "A") (pinfunction "A_A") (pintype "passive"))
      (node (ref "R23") (pin "1") (pinfunction "1_1") (pintype "passive"))
    )
    (net (code "41") (name "Net-(LED9-PadA)") (class "Default")
      (node (ref "LED9") (pin "A") (pinfunction "A_A") (pintype "passive"))
      (node (ref "R24") (pin "1") (pinfunction "1_1") (pintype "passive"))
    )
    (net (code "42") (name "Net-(Q2-G)") (class "Default")
      (node (ref "Q2") (pin "1") (pinfunction "G_1") (pintype "bidirectional"))
      (node (ref "R26") (pin "2") (pinfunction "2_2") (pintype "passive"))
      (node (ref "U7") (pin "2") (pinfunction "ALERT/RDY_2") (pintype "bidirectional"))
    )
    (net (code "43") (name "Net-(U1-OUT)") (class "Default")
      (node (ref "C3") (pin "1") (pinfunction "1_1") (pintype "passive"))
      (node (ref "R2") (pin "1") (pinfunction "1_1") (pintype "passive"))
      (node (ref "S1") (pin "1") (pinfunction "1_1") (pintype "passive"))
      (node (ref "U1") (pin "5") (pinfunction "OUT_5") (pintype "bidirectional"))
      (node (ref "U3") (pin "5") (pinfunction "V+_5") (pintype "bidirectional"))
    )
    (net (code "44") (name "Net-(U2-A2)") (class "Default")
      (node (ref "R1") (pin "1") (pinfunction "1_1") (pintype "passive"))
      (node (ref "U2") (pin "3") (pinfunction "A2_3") (pintype "bidirectional"))
    )
    (net (code "45") (name "Net-(U2-CT1)") (class "Default")
      (node (ref "J1") (pin "5") (pinfunction "5_5") (pintype "passive"))
      (node (ref "U2") (pin "6") (pinfunction "CT1_6") (pintype "bidirectional"))
    )
    (net (code "46") (name "Net-(U2-ET1)") (class "Default")
      (node (ref "J1") (pin "6") (pinfunction "6_6") (pintype "passive"))
      (node (ref "U2") (pin "5") (pinfunction "ET1_5") (pintype "bidirectional"))
    )
    (net (code "47") (name "Net-(U3-DIV)") (class "Default")
      (node (ref "R2") (pin "2") (pinfunction "2_2") (pintype "passive"))
      (node (ref "R3") (pin "2") (pinfunction "2_2") (pintype "passive"))
      (node (ref "U3") (pin "4") (pinfunction "DIV_4") (pintype "bidirectional"))
    )
    (net (code "48") (name "Net-(U3-OUT)") (class "Default")
      (node (ref "R1") (pin "2") (pinfunction "2_2") (pintype "passive"))
      (node (ref "U3") (pin "6") (pinfunction "OUT_6") (pintype "bidirectional"))
    )
    (net (code "49") (name "Net-(U3-SET)") (class "Default")
      (node (ref "R6") (pin "2") (pinfunction "2_2") (pintype "passive"))
      (node (ref "U3") (pin "3") (pinfunction "SET_3") (pintype "bidirectional"))
    )
    (net (code "50") (name "Net-(U4-BOOT)") (class "Default")
      (node (ref "C6") (pin "1") (pinfunction "1_1") (pintype "passive"))
      (node (ref "U4") (pin "6") (pinfunction "BOOT_6") (pintype "bidirectional"))
    )
    (net (code "51") (name "Net-(U4-EN)") (class "Default")
      (node (ref "R4") (pin "1") (pinfunction "1_1") (pintype "passive"))
      (node (ref "R5") (pin "2") (pinfunction "2_2") (pintype "passive"))
      (node (ref "U4") (pin "5") (pinfunction "EN_5") (pintype "bidirectional"))
    )
    (net (code "52") (name "Net-(U4-FB)") (class "Default")
      (node (ref "C10") (pin "2") (pinfunction "2_2") (pintype "passive"))
      (node (ref "R8") (pin "1") (pinfunction "1_1") (pintype "passive"))
      (node (ref "R9") (pin "2") (pinfunction "2_2") (pintype "passive"))
      (node (ref "U4") (pin "4") (pinfunction "FB_4") (pintype "bidirectional"))
    )
    (net (code "53") (name "Net-(U4-VIN)") (class "Default")
      (node (ref "C4") (pin "1") (pinfunction "1_1") (pintype "passive"))
      (node (ref "C5") (pin "1") (pinfunction "1_1") (pintype "passive"))
      (node (ref "F3") (pin "2") (pinfunction "2_2") (pintype "bidirectional"))
      (node (ref "R4") (pin "2") (pinfunction "2_2") (pintype "passive"))
      (node (ref "U4") (pin "3") (pinfunction "VIN_3") (pintype "bidirectional"))
    )
    (net (code "54") (name "Net-(U5-DRAIN)") (class "Default")
      (node (ref "C11") (pin "+") (pinfunction "+_+") (pintype "passive"))
      (node (ref "J2") (pin "2") (pinfunction "5V_2") (pintype "power_in"))
      (node (ref "J2") (pin "4") (pinfunction "5V_4") (pintype "power_in"))
      (node (ref "U5") (pin "10") (pinfunction "OUT_10") (pintype "bidirectional"))
      (node (ref "U5") (pin "9") (pinfunction "VDD_9") (pintype "bidirectional"))
      (node (ref "U5") (pin "P$1") (pinfunction "DRAIN_P$1") (pintype "bidirectional"))
    )
    (net (code "55") (name "Net-(U6-WP)") (class "Default")
      (node (ref "JP1") (pin "2") (pinfunction "2_2") (pintype "passive"))
      (node (ref "R10") (pin "1") (pinfunction "1_1") (pintype "passive"))
      (node (ref "U6") (pin "7") (pinfunction "WP_7") (pintype "bidirectional"))
    )
    (net (code "56") (name "Net-(U7-AIN0)") (class "Default")
      (node (ref "C13") (pin "1") (pinfunction "1_1") (pintype "passive"))
      (node (ref "R15") (pin "2") (pinfunction "2_2") (pintype "passive"))
      (node (ref "U7") (pin "4") (pinfunction "AIN0_4") (pintype "bidirectional"))
    )
    (net (code "57") (name "Net-(U7-AIN1)") (class "Default")
      (node (ref "C14") (pin "1") (pinfunction "1_1") (pintype "passive"))
      (node (ref "R25") (pin "2") (pinfunction "2_2") (pintype "passive"))
      (node (ref "U7") (pin "5") (pinfunction "AIN1_5") (pintype "bidirectional"))
    )
    (net (code "58") (name "Net-(U9-BIAS)") (class "Default")
      (node (ref "R29") (pin "1") (pinfunction "1_1") (pintype "passive"))
      (node (ref "U9") (pin "P$1") (pinfunction "BIAS_P$1") (pintype "bidirectional"))
      (node (ref "U9") (pin "P$2") (pinfunction "REFIN+_P$2") (pintype "bidirectional"))
    )
    (net (code "59") (name "Net-(U9-FORCE+)") (class "Default")
      (node (ref "J6") (pin "1") (pinfunction "1_1") (pintype "passive"))
      (node (ref "U9") (pin "P$5") (pinfunction "FORCE+_P$5") (pintype "bidirectional"))
      (node (ref "U9") (pin "P$6") (pinfunction "FORCE2_P$6") (pintype "bidirectional"))
    )
    (net (code "60") (name "Net-(U9-FORCE-)") (class "Default")
      (node (ref "C18") (pin "2") (pinfunction "2_2") (pintype "passive"))
      (node (ref "J6") (pin "3") (pinfunction "3_3") (pintype "passive"))
      (node (ref "U9") (pin "P$8") (pinfunction "RTDIN-_P$8") (pintype "bidirectional"))
      (node (ref "U9") (pin "P$9") (pinfunction "FORCE-_P$9") (pintype "bidirectional"))
    )
    (net (code "61") (name "Net-(U9-ISENSOR)") (class "Default")
      (node (ref "R29") (pin "2") (pinfunction "2_2") (pintype "passive"))
      (node (ref "U9") (pin "P$3") (pinfunction "REFIN-_P$3") (pintype "bidirectional"))
      (node (ref "U9") (pin "P$4") (pinfunction "ISENSOR_P$4") (pintype "bidirectional"))
    )
    (net (code "62") (name "Net-(U9-RTDIN+)") (class "Default")
      (node (ref "C18") (pin "1") (pinfunction "1_1") (pintype "passive"))
      (node (ref "J6") (pin "2") (pinfunction "2_2") (pintype "passive"))
      (node (ref "U9") (pin "P$7") (pinfunction "RTDIN+_P$7") (pintype "bidirectional"))
    )
    (net (code "63") (name "Net-(U10-PRN)") (class "Default")
      (node (ref "J7") (pin "GND") (pinfunction "GND_GND") (pintype "bidirectional"))
      (node (ref "U10") (pin "PGND") (pinfunction "PRN_PGND") (pintype "bidirectional"))
    )
    (net (code "64") (name "Net-(U11-BIAS)") (class "Default")
      (node (ref "R30") (pin "1") (pinfunction "1_1") (pintype "passive"))
      (node (ref "U11") (pin "P$1") (pinfunction "BIAS_P$1") (pintype "bidirectional"))
      (node (ref "U11") (pin "P$2") (pinfunction "REFIN+_P$2") (pintype "bidirectional"))
    )
    (net (code "65") (name "Net-(U11-FORCE+)") (class "Default")
      (node (ref "J8") (pin "1") (pinfunction "1_1") (pintype "passive"))
      (node (ref "U11") (pin "P$5") (pinfunction "FORCE+_P$5") (pintype "bidirectional"))
      (node (ref "U11") (pin "P$6") (pinfunction "FORCE2_P$6") (pintype "bidirectional"))
    )
    (net (code "66") (name "Net-(U11-FORCE-)") (class "Default")
      (node (ref "C22") (pin "2") (pinfunction "2_2") (pintype "passive"))
      (node (ref "J8") (pin "3") (pinfunction "3_3") (pintype "passive"))
      (node (ref "U11") (pin "P$8") (pinfunction "RTDIN-_P$8") (pintype "bidirectional"))
      (node (ref "U11") (pin "P$9") (pinfunction "FORCE-_P$9") (pintype "bidirectional"))
    )
    (net (code "67") (name "Net-(U11-ISENSOR)") (class "Default")
      (node (ref "R30") (pin "2") (pinfunction "2_2") (pintype "passive"))
      (node (ref "U11") (pin "P$3") (pinfunction "REFIN-_P$3") (pintype "bidirectional"))
      (node (ref "U11") (pin "P$4") (pinfunction "ISENSOR_P$4") (pintype "bidirectional"))
    )
    (net (code "68") (name "Net-(U11-RTDIN+)") (class "Default")
      (node (ref "C22") (pin "1") (pinfunction "1_1") (pintype "passive"))
      (node (ref "J8") (pin "2") (pinfunction "2_2") (pintype "passive"))
      (node (ref "U11") (pin "P$7") (pinfunction "RTDIN+_P$7") (pintype "bidirectional"))
    )
    (net (code "69") (name "P1ISENSE") (class "Default")
      (node (ref "Q1") (pin "P$1") (pinfunction "S_P$1") (pintype "passive"))
      (node (ref "Q1") (pin "P$2") (pinfunction "S_P$2") (pintype "passive"))
      (node (ref "Q1") (pin "P$3") (pinfunction "S_P$3") (pintype "passive"))
      (node (ref "R15") (pin "1") (pinfunction "1_1") (pintype "passive"))
      (node (ref "R27") (pin "1") (pinfunction "1_1") (pintype "passive"))
    )
    (net (code "70") (name "P1PWM") (class "Default")
      (node (ref "Q1") (pin "P$4") (pinfunction "G_P$4") (pintype "passive"))
      (node (ref "U8") (pin "16") (pinfunction "CH9_16") (pintype "bidirectional"))
    )
    (net (code "71") (name "P2ISENSE") (class "Default")
      (node (ref "Q3") (pin "P$1") (pinfunction "S_P$1") (pintype "passive"))
      (node (ref "Q3") (pin "P$2") (pinfunction "S_P$2") (pintype "passive"))
      (node (ref "Q3") (pin "P$3") (pinfunction "S_P$3") (pintype "passive"))
      (node (ref "R25") (pin "1") (pinfunction "1_1") (pintype "passive"))
      (node (ref "R28") (pin "1") (pinfunction "1_1") (pintype "passive"))
    )
    (net (code "72") (name "P2PWM") (class "Default")
      (node (ref "Q3") (pin "P$4") (pinfunction "G_P$4") (pintype "passive"))
      (node (ref "U8") (pin "15") (pinfunction "CH8_15") (pintype "bidirectional"))
    )
    (net (code "73") (name "PHGOOD") (class "Default")
      (node (ref "LED6") (pin "C") (pinfunction "C_C") (pintype "passive"))
      (node (ref "U8") (pin "8") (pinfunction "CH2_8") (pintype "bidirectional"))
    )
    (net (code "74") (name "PON") (class "Default")
      (node (ref "J2") (pin "33") (pinfunction "GP13_33") (pintype "bidirectional"))
      (node (ref "S1") (pin "3") (pinfunction "2_3") (pintype "passive"))
      (node (ref "U3") (pin "1") (pinfunction "IN_1") (pintype "bidirectional"))
    )
    (net (code "75") (name "PWM0") (class "Default")
      (node (ref "U8") (pin "11") (pinfunction "CH5_11") (pintype "bidirectional"))
    )
    (net (code "76") (name "PWM1") (class "Default")
      (node (ref "U8") (pin "12") (pinfunction "CH6_12") (pintype "bidirectional"))
    )
    (net (code "77") (name "PWM2") (class "Default")
      (node (ref "U8") (pin "13") (pinfunction "CH7_13") (pintype "bidirectional"))
    )
    (net (code "78") (name "RDY0") (class "Default")
      (node (ref "J2") (pin "31") (pinfunction "GP6_31") (pintype "bidirectional"))
      (node (ref "U9") (pin "P$18") (pinfunction "~{RDY}_P$18") (pintype "bidirectional"))
    )
    (net (code "79") (name "RDY1") (class "Default")
      (node (ref "J2") (pin "32") (pinfunction "GP12_32") (pintype "bidirectional"))
      (node (ref "U11") (pin "P$18") (pinfunction "~{RDY}_P$18") (pintype "bidirectional"))
    )
    (net (code "80") (name "RX") (class "Default")
      (node (ref "J2") (pin "8") (pinfunction "TXO_8") (pintype "output"))
      (node (ref "U10") (pin "RX") (pinfunction "RX_RX") (pintype "bidirectional"))
    )
    (net (code "81") (name "SCL") (class "Default")
      (node (ref "J2") (pin "5") (pinfunction "SCL_5") (pintype "bidirectional"))
      (node (ref "J3") (pin "P$4") (pinfunction "5_P$4") (pintype "passive"))
      (node (ref "R14") (pin "1") (pinfunction "1_1") (pintype "passive"))
      (node (ref "U7") (pin "10") (pinfunction "SCL_10") (pintype "bidirectional"))
      (node (ref "U8") (pin "26") (pinfunction "SCL_26") (pintype "bidirectional"))
    )
    (net (code "82") (name "SCLK") (class "Default")
      (node (ref "J2") (pin "23") (pinfunction "SCLK_23") (pintype "output"))
      (node (ref "J3") (pin "P$6") (pinfunction "7_P$6") (pintype "passive"))
      (node (ref "U11") (pin "P$12") (pinfunction "CLK_P$12") (pintype "bidirectional"))
      (node (ref "U9") (pin "P$12") (pinfunction "CLK_P$12") (pintype "bidirectional"))
    )
    (net (code "83") (name "SDA") (class "Default")
      (node (ref "J2") (pin "3") (pinfunction "SDA_3") (pintype "bidirectional"))
      (node (ref "J3") (pin "P$2") (pinfunction "3_P$2") (pintype "passive"))
      (node (ref "R13") (pin "1") (pinfunction "1_1") (pintype "passive"))
      (node (ref "U7") (pin "9") (pinfunction "SDA_9") (pintype "bidirectional"))
      (node (ref "U8") (pin "27") (pinfunction "SDA_27") (pintype "bidirectional"))
    )
    (net (code "84") (name "SS0") (class "Default")
      (node (ref "J2") (pin "24") (pinfunction "CE0_24") (pintype "output"))
      (node (ref "U9") (pin "P$13") (pinfunction "~{CS}_P$13") (pintype "bidirectional"))
    )
    (net (code "85") (name "SS1") (class "Default")
      (node (ref "J2") (pin "26") (pinfunction "CE1_26") (pintype "output"))
      (node (ref "U11") (pin "P$13") (pinfunction "~{CS}_P$13") (pintype "bidirectional"))
    )
    (net (code "86") (name "T1GOOD") (class "Default")
      (node (ref "LED4") (pin "C") (pinfunction "C_C") (pintype "passive"))
      (node (ref "U8") (pin "6") (pinfunction "CH0_6") (pintype "bidirectional"))
    )
    (net (code "87") (name "T2GOOD") (class "Default")
      (node (ref "LED5") (pin "C") (pinfunction "C_C") (pintype "passive"))
      (node (ref "U8") (pin "7") (pinfunction "CH1_7") (pintype "bidirectional"))
    )
    (net (code "88") (name "TX") (class "Default")
      (node (ref "J2") (pin "10") (pinfunction "RXI_10") (pintype "input"))
      (node (ref "U10") (pin "TX") (pinfunction "TX_TX") (pintype "bidirectional"))
    )
    (net (code "89") (name "unconnected-(U2-A1-Pad1)") (class "Default")
      (node (ref "U2") (pin "1") (pinfunction "A1_1") (pintype "bidirectional"))
    )
    (net (code "90") (name "unconnected-(U2-C1-Pad2)") (class "Default")
      (node (ref "U2") (pin "2") (pinfunction "C1_2") (pintype "bidirectional"))
    )
    (net (code "91") (name "unconnected-(U2-CT2-Pad8)") (class "Default")
      (node (ref "U2") (pin "8") (pinfunction "CT2_8") (pintype "bidirectional"))
    )
    (net (code "92") (name "unconnected-(U2-ET2-Pad7)") (class "Default")
      (node (ref "U2") (pin "7") (pinfunction "ET2_7") (pintype "bidirectional"))
    )
    (net (code "93") (name "unconnected-(U7-AIN2-Pad6)") (class "Default")
      (node (ref "U7") (pin "6") (pinfunction "AIN2_6") (pintype "bidirectional"))
    )
    (net (code "94") (name "unconnected-(U7-AIN3-Pad7)") (class "Default")
      (node (ref "U7") (pin "7") (pinfunction "AIN3_7") (pintype "bidirectional"))
    )
    (net (code "95") (name "unconnected-(U8-CH10-Pad17)") (class "Default")
      (node (ref "U8") (pin "17") (pinfunction "CH10_17") (pintype "bidirectional"))
    )
    (net (code "96") (name "unconnected-(U8-CH11-Pad18)") (class "Default")
      (node (ref "U8") (pin "18") (pinfunction "CH11_18") (pintype "bidirectional"))
    )
    (net (code "97") (name "unconnected-(U8-CH12-Pad19)") (class "Default")
      (node (ref "U8") (pin "19") (pinfunction "CH12_19") (pintype "bidirectional"))
    )
    (net (code "98") (name "unconnected-(U8-CH13-Pad20)") (class "Default")
      (node (ref "U8") (pin "20") (pinfunction "CH13_20") (pintype "bidirectional"))
    )
    (net (code "99") (name "unconnected-(U8-CH14-Pad21)") (class "Default")
      (node (ref "U8") (pin "21") (pinfunction "CH14_21") (pintype "bidirectional"))
    )
    (net (code "100") (name "unconnected-(U8-CH15-Pad22)") (class "Default")
      (node (ref "U8") (pin "22") (pinfunction "CH15_22") (pintype "bidirectional"))
    )
  )
)
